# Sheet1.net
KiCad netlist of a schematic drawn in Altium Designer
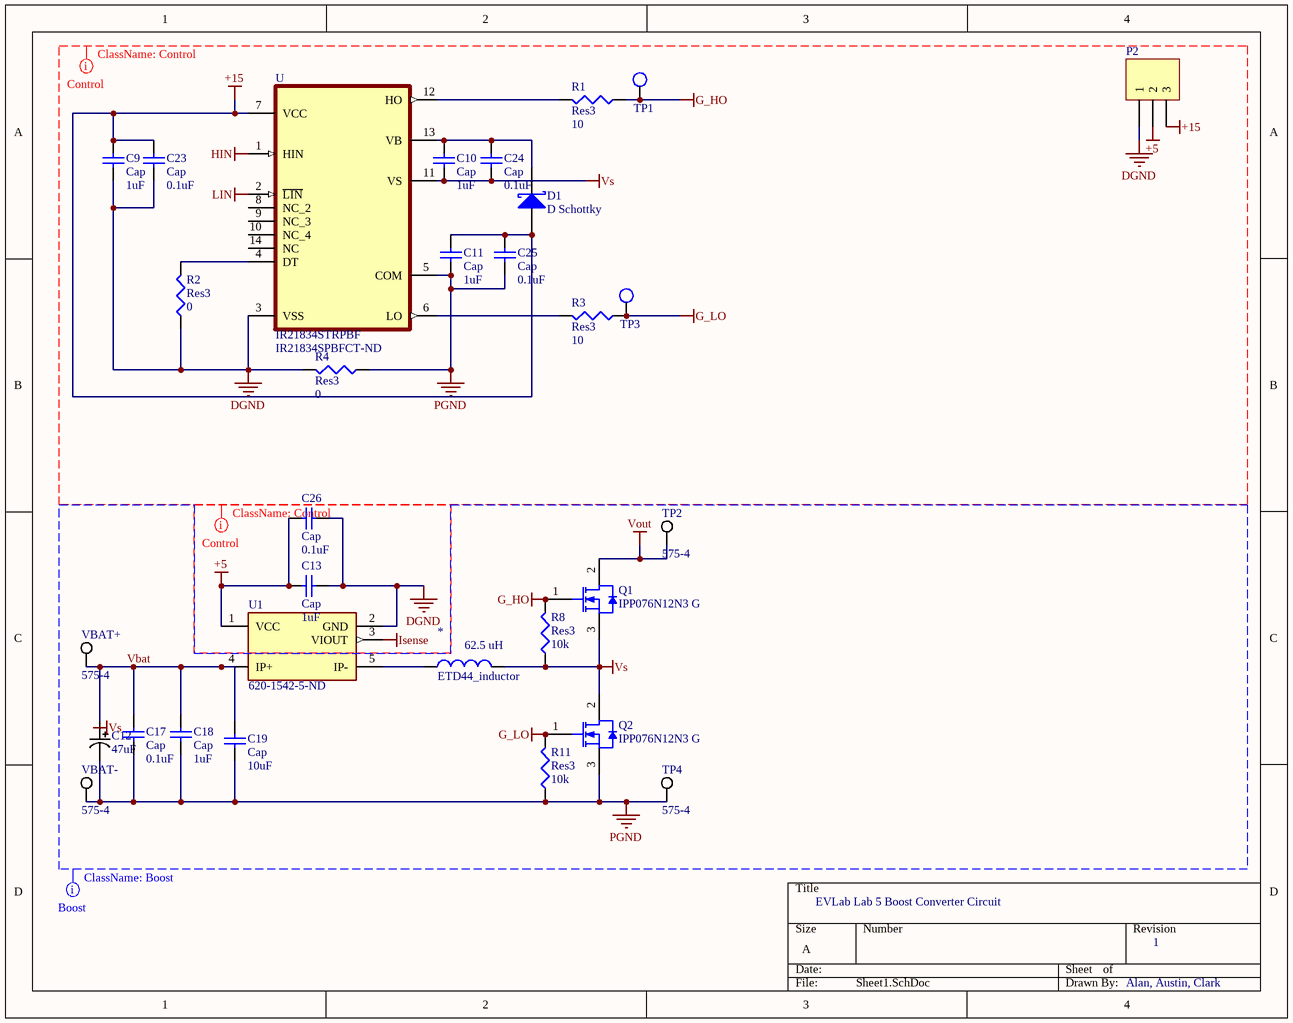
[diagram p0: Sheet1.SchDoc]

(export (version "E")
  (design (tool "Eeschema 10.0.6"))
  (components
    (comp (ref "*")
      (value "ETD44_inductor")
      (footprint "ETD44")
      (libsource (lib "Schlib1") (part "ETD44_inductor"))
    )
    (comp (ref "C9")
      (value "Cap")
      (footprint "C0603")
      (description "Capacitor")
      (fields (field (name "ALTIUM_VALUE") "1uF") (field (name "PUBLISHER") "Altium Limited"))
      (libsource (lib "Schlib1") (part "Cap"))
    )
    (comp (ref "C10")
      (value "Cap")
      (footprint "C0603")
      (description "Capacitor")
      (fields (field (name "ALTIUM_VALUE") "1uF") (field (name "PUBLISHER") "Altium Limited"))
      (libsource (lib "Schlib1") (part "Cap"))
    )
    (comp (ref "C11")
      (value "Cap")
      (footprint "C0603")
      (description "Capacitor")
      (fields (field (name "ALTIUM_VALUE") "1uF") (field (name "PUBLISHER") "Altium Limited"))
      (libsource (lib "Schlib1") (part "Cap"))
    )
    (comp (ref "C12")
      (value "47uF")
      (footprint "CAP_PC_10X10")
      (description "CAP ALUM POLY 47UF 20% 80V SMD")
      (fields
        (field (name "MANUFACTURER_PART_NUMBER") "KEMET")
        (field (name "MANUFACTURER PART NUMBER") "A767MU476M1KLAE040")
        (field (name "COPYRIGHT") "Copyright (C) 2018 Accelerated Designs. All rights reserved")
      )
      (libsource (lib "Schlib1") (part "A767MU476M1KLAE040"))
    )
    (comp (ref "C13")
      (value "Cap")
      (footprint "C0603")
      (description "Capacitor")
      (fields (field (name "ALTIUM_VALUE") "1uF") (field (name "PUBLISHER") "Altium Limited"))
      (libsource (lib "Schlib1") (part "Cap"))
    )
    (comp (ref "C17")
      (value "Cap")
      (footprint "C0603")
      (description "Capacitor")
      (fields (field (name "ALTIUM_VALUE") "0.1uF") (field (name "PUBLISHER") "Altium Limited"))
      (libsource (lib "Schlib1") (part "Cap"))
    )
    (comp (ref "C18")
      (value "Cap")
      (footprint "C0603")
      (description "Capacitor")
      (fields (field (name "ALTIUM_VALUE") "1uF") (field (name "PUBLISHER") "Altium Limited"))
      (libsource (lib "Schlib1") (part "Cap"))
    )
    (comp (ref "C19")
      (value "Cap")
      (footprint "C0603")
      (description "Capacitor")
      (fields (field (name "ALTIUM_VALUE") "10uF") (field (name "PUBLISHER") "Altium Limited"))
      (libsource (lib "Schlib1") (part "Cap"))
    )
    (comp (ref "C23")
      (value "Cap")
      (footprint "C0603")
      (description "Capacitor")
      (fields (field (name "ALTIUM_VALUE") "0.1uF") (field (name "PUBLISHER") "Altium Limited"))
      (libsource (lib "Schlib1") (part "Cap"))
    )
    (comp (ref "C24")
      (value "Cap")
      (footprint "C0603")
      (description "Capacitor")
      (fields (field (name "ALTIUM_VALUE") "0.1uF") (field (name "PUBLISHER") "Altium Limited"))
      (libsource (lib "Schlib1") (part "Cap"))
    )
    (comp (ref "C25")
      (value "Cap")
      (footprint "C0603")
      (description "Capacitor")
      (fields (field (name "ALTIUM_VALUE") "0.1uF") (field (name "PUBLISHER") "Altium Limited"))
      (libsource (lib "Schlib1") (part "Cap"))
    )
    (comp (ref "C26")
      (value "Cap")
      (footprint "C0603")
      (description "Capacitor")
      (fields (field (name "ALTIUM_VALUE") "0.1uF") (field (name "PUBLISHER") "Altium Limited"))
      (libsource (lib "Schlib1") (part "Cap"))
    )
    (comp (ref "D1")
      (value "D Schottky")
      (footprint "SMB")
      (description "Schottky Diode")
      (fields (field (name "PUBLISHER") "Altium Limited"))
      (libsource (lib "Miscellaneous Devices") (part "D Schottky"))
    )
    (comp (ref "P2")
      (value "MHDR1X3")
      (footprint "MHDR1X3")
      (description "Header, 3-Pin")
      (fields (field (name "PUBLISHER") "Altium Limited"))
      (libsource (lib "Miscellaneous Connectors") (part "MHDR1X3"))
    )
    (comp (ref "Q1")
      (value "IPP076N12N3 G")
      (footprint "INF-PG-TO220-3-1_A_V")
      (fields (field (name "MANUFACTURER") "Infineon"))
      (libsource (lib "Schlib1") (part "IPP076N12N3 G"))
    )
    (comp (ref "Q2")
      (value "IPP076N12N3 G")
      (footprint "INF-PG-TO220-3-1_A_V")
      (fields (field (name "MANUFACTURER") "Infineon"))
      (libsource (lib "Schlib1") (part "IPP076N12N3 G"))
    )
    (comp (ref "R1")
      (value "Res3")
      (footprint "J1-0603")
      (description "Resistor")
      (fields (field (name "ALTIUM_VALUE") "10") (field (name "PUBLISHER") "Altium Limited"))
      (libsource (lib "Miscellaneous Devices") (part "Res3"))
    )
    (comp (ref "R2")
      (value "Res3")
      (footprint "J1-0603")
      (description "Resistor")
      (fields (field (name "ALTIUM_VALUE") "0") (field (name "PUBLISHER") "Altium Limited"))
      (libsource (lib "Miscellaneous Devices") (part "Res3"))
    )
    (comp (ref "R3")
      (value "Res3")
      (footprint "J1-0603")
      (description "Resistor")
      (fields (field (name "ALTIUM_VALUE") "10") (field (name "PUBLISHER") "Altium Limited"))
      (libsource (lib "Miscellaneous Devices") (part "Res3"))
    )
    (comp (ref "R4")
      (value "Res3")
      (footprint "J1-0603")
      (description "Resistor")
      (fields (field (name "ALTIUM_VALUE") "0") (field (name "PUBLISHER") "Altium Limited"))
      (libsource (lib "Miscellaneous Devices") (part "Res3"))
    )
    (comp (ref "R8")
      (value "Res3")
      (footprint "J1-0603")
      (description "Resistor")
      (fields (field (name "ALTIUM_VALUE") "10k") (field (name "PUBLISHER") "Altium Limited"))
      (libsource (lib "Miscellaneous Devices") (part "Res3"))
    )
    (comp (ref "R11")
      (value "Res3")
      (footprint "J1-0603")
      (description "Resistor")
      (fields (field (name "ALTIUM_VALUE") "10k") (field (name "PUBLISHER") "Altium Limited"))
      (libsource (lib "Miscellaneous Devices") (part "Res3"))
    )
    (comp (ref "TP1")
      (value "Test Point")
      (footprint "Test Point - TH")
      (libsource (lib "Schlib1") (part "Test Point"))
    )
    (comp (ref "TP2")
      (value "575-4")
      (footprint "KSTN-575-4")
      (description "Banana Jack, Non-Insulated, 1-Pin THD, RoHS, Bulk")
      (fields (field (name "MANUFACTURER") "Keystone-Electronics"))
      (libsource (lib "Schlib1") (part "CMP-2000-05649-1"))
    )
    (comp (ref "TP3")
      (value "Test Point")
      (footprint "Test Point - TH")
      (libsource (lib "Schlib1") (part "Test Point"))
    )
    (comp (ref "TP4")
      (value "575-4")
      (footprint "KSTN-575-4")
      (description "Banana Jack, Non-Insulated, 1-Pin THD, RoHS, Bulk")
      (fields (field (name "MANUFACTURER") "Keystone-Electronics"))
      (libsource (lib "Schlib1") (part "CMP-2000-05649-1"))
    )
    (comp (ref "U")
      (value "IR21834STRPBF")
      (footprint "SOIC127P600X175-14N")
      (description "INTERNATIONAL RECTIFIER   IR21834STRPBF   MOSFET DRIVER, HALF BRIDGE, SOIC-14, FULL REEL")
      (fields
        (field (name "DIGI-KEY_PART_NUMBER") "IR21834SPBFCT-ND")
        (field (name "MF") "Infineon Technologies")
        (field (name "SUPPLIER PART NUMBER 3") "IR21834SPBFCT-ND")
      )
      (libsource (lib "Schlib1") (part "IR21834STRPBF"))
    )
    (comp (ref "U1")
      (value "ACS770KCB-150B-PFF-T")
      (footprint "Allegro_MicroSystems_CB-PFF-5_0")
      (fields
        (field (name "MANUFACTURER") "Allegro MicroSystems")
        (field (name "MANUFACTURER PART NUMBER") "ACS770LCB-050U-PFF-T")
        (field (name "SUPPLIER PART NUMBER 1") "620-1542-5-ND")
      )
      (libsource (lib "Schlib1") (part "ACS770KCB-150B-PFF-T"))
    )
    (comp (ref "VBAT+")
      (value "575-4")
      (footprint "KSTN-575-4")
      (description "Banana Jack, Non-Insulated, 1-Pin THD, RoHS, Bulk")
      (fields (field (name "MANUFACTURER") "Keystone-Electronics"))
      (libsource (lib "Schlib1") (part "CMP-2000-05649-1"))
    )
    (comp (ref "VBAT-")
      (value "575-4")
      (footprint "KSTN-575-4")
      (description "Banana Jack, Non-Insulated, 1-Pin THD, RoHS, Bulk")
      (fields (field (name "MANUFACTURER") "Keystone-Electronics"))
      (libsource (lib "Schlib1") (part "CMP-2000-05649-1"))
    )
  )
  (nets
    (net (code "1") (name "+5") (class "Default")
      (node (ref "C13") (pin "2") (pinfunction "2_2") (pintype "passive"))
      (node (ref "C26") (pin "2") (pinfunction "2_2") (pintype "passive"))
      (node (ref "P2") (pin "2") (pinfunction "2_2") (pintype "passive"))
      (node (ref "U1") (pin "1") (pinfunction "VCC_1") (pintype "power_in"))
    )
    (net (code "2") (name "+15") (class "Default")
      (node (ref "C11") (pin "2") (pinfunction "2_2") (pintype "passive"))
      (node (ref "C23") (pin "1") (pinfunction "1_1") (pintype "passive"))
      (node (ref "C25") (pin "1") (pinfunction "1_1") (pintype "passive"))
      (node (ref "C9") (pin "2") (pinfunction "2_2") (pintype "passive"))
      (node (ref "D1") (pin "1") (pinfunction "A_1") (pintype "passive"))
      (node (ref "P2") (pin "3") (pinfunction "3_3") (pintype "passive"))
      (node (ref "U") (pin "7") (pinfunction "VCC_7") (pintype "power_in"))
    )
    (net (code "3") (name "/Vbat") (class "Default")
      (node (ref "C12") (pin "1") (pinfunction "1_1") (pintype "passive"))
      (node (ref "C17") (pin "2") (pinfunction "2_2") (pintype "passive"))
      (node (ref "C18") (pin "2") (pinfunction "2_2") (pintype "passive"))
      (node (ref "C19") (pin "2") (pinfunction "2_2") (pintype "passive"))
      (node (ref "U1") (pin "4") (pinfunction "IP+_4") (pintype "passive"))
      (node (ref "VBAT+") (pin "1") (pinfunction "1_1") (pintype "passive"))
    )
    (net (code "4") (name "DGND") (class "Default")
      (node (ref "C13") (pin "1") (pinfunction "1_1") (pintype "passive"))
      (node (ref "C23") (pin "2") (pinfunction "2_2") (pintype "passive"))
      (node (ref "C26") (pin "1") (pinfunction "1_1") (pintype "passive"))
      (node (ref "C9") (pin "1") (pinfunction "1_1") (pintype "passive"))
      (node (ref "P2") (pin "1") (pinfunction "1_1") (pintype "passive"))
      (node (ref "R2") (pin "1") (pinfunction "1_1") (pintype "passive"))
      (node (ref "R4") (pin "2") (pinfunction "2_2") (pintype "passive"))
      (node (ref "U") (pin "3") (pinfunction "VSS_3") (pintype "power_in"))
      (node (ref "U1") (pin "2") (pinfunction "GND_2") (pintype "power_in"))
    )
    (net (code "5") (name "G_HO") (class "Default")
      (node (ref "Q1") (pin "1") (pinfunction "GATE_1") (pintype "passive"))
      (node (ref "R1") (pin "1") (pinfunction "1_1") (pintype "passive"))
      (node (ref "R8") (pin "2") (pinfunction "2_2") (pintype "passive"))
      (node (ref "TP1") (pin "1") (pinfunction "1_1") (pintype "passive"))
    )
    (net (code "6") (name "G_LO") (class "Default")
      (node (ref "Q2") (pin "1") (pinfunction "GATE_1") (pintype "passive"))
      (node (ref "R11") (pin "2") (pinfunction "2_2") (pintype "passive"))
      (node (ref "R3") (pin "1") (pinfunction "1_1") (pintype "passive"))
      (node (ref "TP3") (pin "1") (pinfunction "1_1") (pintype "passive"))
    )
    (net (code "7") (name "HIN") (class "Default")
      (node (ref "U") (pin "1") (pinfunction "HIN_1") (pintype "input"))
    )
    (net (code "8") (name "Isense") (class "Default")
      (node (ref "U1") (pin "3") (pinfunction "VIOUT_3") (pintype "output"))
    )
    (net (code "9") (name "LIN") (class "Default")
      (node (ref "U") (pin "2") (pinfunction "~{LIN}_2") (pintype "input"))
    )
    (net (code "10") (name "Net-(D1-K)") (class "Default")
      (node (ref "C10") (pin "2") (pinfunction "2_2") (pintype "passive"))
      (node (ref "C24") (pin "1") (pinfunction "1_1") (pintype "passive"))
      (node (ref "D1") (pin "2") (pinfunction "K_2") (pintype "passive"))
      (node (ref "U") (pin "13") (pinfunction "VB_13") (pintype "passive"))
    )
    (net (code "11") (name "Net-(U-DT)") (class "Default")
      (node (ref "R2") (pin "2") (pinfunction "2_2") (pintype "passive"))
      (node (ref "U") (pin "4") (pinfunction "DT_4") (pintype "passive"))
    )
    (net (code "12") (name "Net-(U-HO)") (class "Default")
      (node (ref "R1") (pin "2") (pinfunction "2_2") (pintype "passive"))
      (node (ref "U") (pin "12") (pinfunction "HO_12") (pintype "output"))
    )
    (net (code "13") (name "Net-(U-LO)") (class "Default")
      (node (ref "R3") (pin "2") (pinfunction "2_2") (pintype "passive"))
      (node (ref "U") (pin "6") (pinfunction "LO_6") (pintype "output"))
    )
    (net (code "14") (name "Net-(U1-IP-)") (class "Default")
      (node (ref "*") (pin "1") (pinfunction "1_1") (pintype "passive"))
      (node (ref "U1") (pin "5") (pinfunction "IP-_5") (pintype "passive"))
    )
    (net (code "15") (name "PGND") (class "Default")
      (node (ref "C11") (pin "1") (pinfunction "1_1") (pintype "passive"))
      (node (ref "C12") (pin "2") (pinfunction "2_2") (pintype "passive"))
      (node (ref "C17") (pin "1") (pinfunction "1_1") (pintype "passive"))
      (node (ref "C18") (pin "1") (pinfunction "1_1") (pintype "passive"))
      (node (ref "C19") (pin "1") (pinfunction "1_1") (pintype "passive"))
      (node (ref "C25") (pin "2") (pinfunction "2_2") (pintype "passive"))
      (node (ref "Q2") (pin "3") (pinfunction "SOURCE_3") (pintype "passive"))
      (node (ref "R11") (pin "1") (pinfunction "1_1") (pintype "passive"))
      (node (ref "R4") (pin "1") (pinfunction "1_1") (pintype "passive"))
      (node (ref "TP4") (pin "1") (pinfunction "1_1") (pintype "passive"))
      (node (ref "U") (pin "5") (pinfunction "COM_5") (pintype "passive"))
      (node (ref "VBAT-") (pin "1") (pinfunction "1_1") (pintype "passive"))
    )
    (net (code "16") (name "Vout") (class "Default")
      (node (ref "Q1") (pin "2") (pinfunction "DRAIN_2") (pintype "passive"))
      (node (ref "TP2") (pin "1") (pinfunction "1_1") (pintype "passive"))
    )
    (net (code "17") (name "Vs") (class "Default")
      (node (ref "*") (pin "2") (pinfunction "2_2") (pintype "passive"))
      (node (ref "C10") (pin "1") (pinfunction "1_1") (pintype "passive"))
      (node (ref "C24") (pin "2") (pinfunction "2_2") (pintype "passive"))
      (node (ref "Q1") (pin "3") (pinfunction "SOURCE_3") (pintype "passive"))
      (node (ref "Q2") (pin "2") (pinfunction "DRAIN_2") (pintype "passive"))
      (node (ref "R8") (pin "1") (pinfunction "1_1") (pintype "passive"))
      (node (ref "U") (pin "11") (pinfunction "VS_11") (pintype "passive"))
    )
    (net (code "18") (name "unconnected-(U-NC-Pad14)") (class "Default")
      (node (ref "U") (pin "14") (pinfunction "NC_14") (pintype "tri_state"))
    )
    (net (code "19") (name "unconnected-(U-NC_2-Pad8)") (class "Default")
      (node (ref "U") (pin "8") (pinfunction "NC_2_8") (pintype "tri_state"))
    )
    (net (code "20") (name "unconnected-(U-NC_3-Pad9)") (class "Default")
      (node (ref "U") (pin "9") (pinfunction "NC_3_9") (pintype "tri_state"))
    )
    (net (code "21") (name "unconnected-(U-NC_4-Pad10)") (class "Default")
      (node (ref "U") (pin "10") (pinfunction "NC_4_10") (pintype "tri_state"))
    )
  )
)
